# M785dec.net
KiCad netlist of a schematic drawn in EAGLE
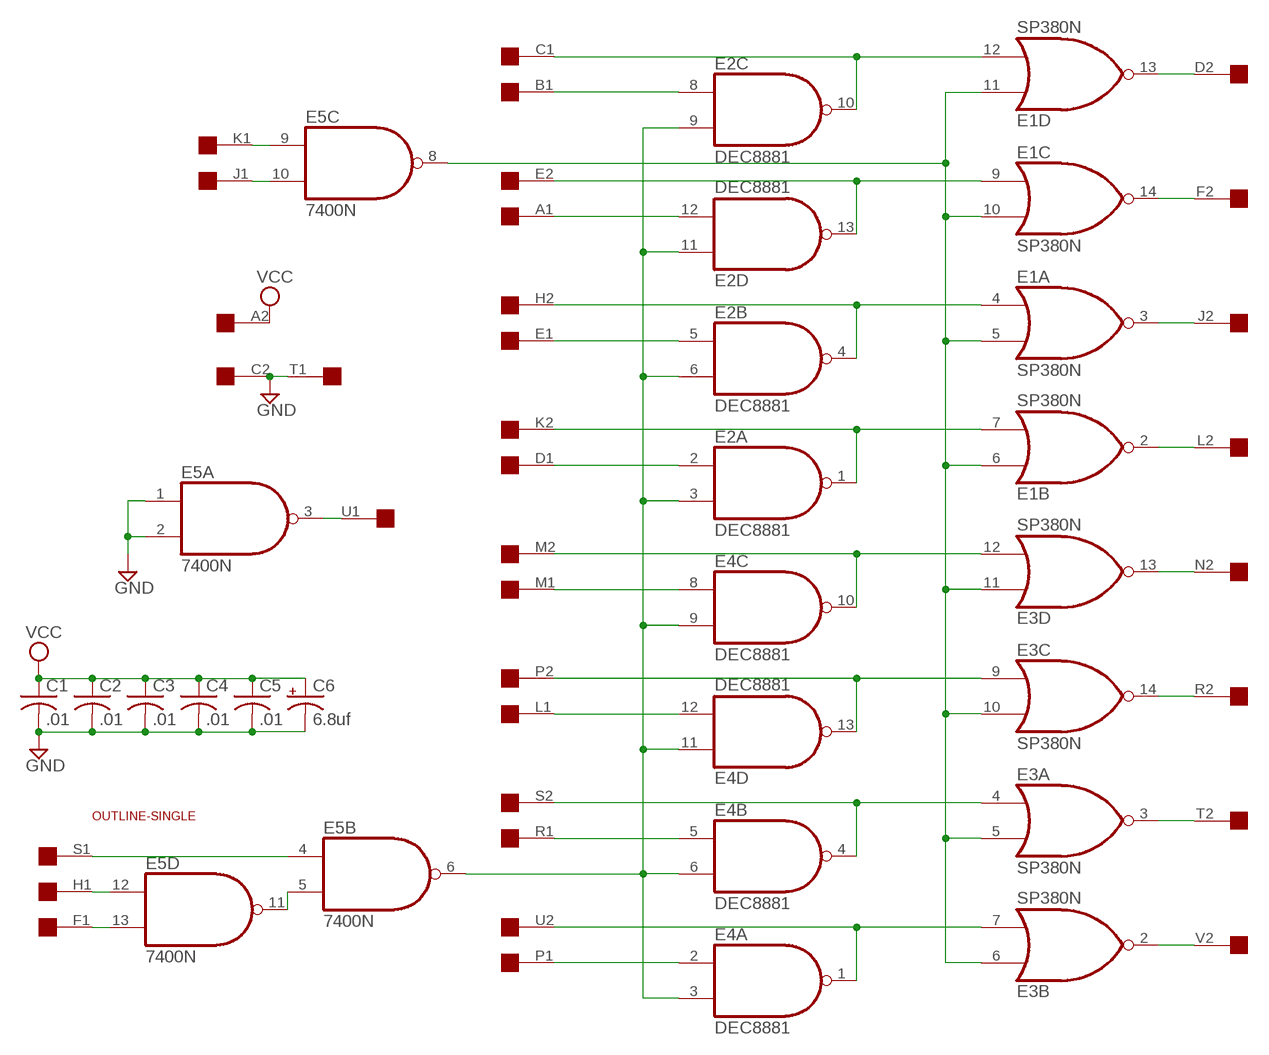
[diagram p0: schematic, sheet 1]

(export (version "E")
  (design (tool "Eeschema 10.0.6"))
  (components
    (comp (ref "C1")
      (value ".01")
      (footprint "eagle-import:C050-025X075")
      (libsource (lib "eagle-import") (part "C-US050-025X075"))
    )
    (comp (ref "C2")
      (value ".01")
      (footprint "eagle-import:C050-025X075")
      (libsource (lib "eagle-import") (part "C-US050-025X075"))
    )
    (comp (ref "C3")
      (value ".01")
      (footprint "eagle-import:C050-025X075")
      (libsource (lib "eagle-import") (part "C-US050-025X075"))
    )
    (comp (ref "C4")
      (value ".01")
      (footprint "eagle-import:C050-025X075")
      (libsource (lib "eagle-import") (part "C-US050-025X075"))
    )
    (comp (ref "C5")
      (value ".01")
      (footprint "eagle-import:C050-025X075")
      (libsource (lib "eagle-import") (part "C-US050-025X075"))
    )
    (comp (ref "C6")
      (value "6.8uf")
      (footprint "eagle-import:E15-5")
      (libsource (lib "eagle-import") (part "CPOL-USE15-5AXIAL"))
    )
    (comp (ref "E1")
      (value "SP380N")
      (footprint "eagle-import:DIL14")
      (libsource (lib "eagle-import") (part "SP380N"))
    )
    (comp (ref "E2")
      (value "DEC8881")
      (footprint "eagle-import:DIL14")
      (libsource (lib "eagle-import") (part "N8881N"))
    )
    (comp (ref "E3")
      (value "SP380N")
      (footprint "eagle-import:DIL14")
      (libsource (lib "eagle-import") (part "SP380N"))
    )
    (comp (ref "E4")
      (value "DEC8881")
      (footprint "eagle-import:DIL14")
      (libsource (lib "eagle-import") (part "N8881N"))
    )
    (comp (ref "E5")
      (value "7400N")
      (footprint "eagle-import:DIL14")
      (libsource (lib "eagle-import") (part "7400N"))
    )
    (comp (ref "U$1")
      (value "SINGLE")
      (footprint "eagle-import:EDGE-CON2")
      (libsource (lib "eagle-import") (part "SINGLE"))
    )
    (comp (ref "U$2")
      (value "OUTLINE-SINGLE")
      (footprint "eagle-import:SINGLE")
      (libsource (lib "eagle-import") (part "OUTLINE-SINGLE"))
    )
  )
  (nets
    (net (code "1") (name "GND") (class "Default")
      (node (ref "C1") (pin "2") (pinfunction "2_2") (pintype "passive"))
      (node (ref "C2") (pin "2") (pinfunction "2_2") (pintype "passive"))
      (node (ref "C3") (pin "2") (pinfunction "2_2") (pintype "passive"))
      (node (ref "C4") (pin "2") (pinfunction "2_2") (pintype "passive"))
      (node (ref "C5") (pin "2") (pinfunction "2_2") (pintype "passive"))
      (node (ref "C6") (pin "-") (pinfunction "-_-") (pintype "passive"))
      (node (ref "E5") (pin "1") (pinfunction "I0_1") (pintype "input"))
      (node (ref "E5") (pin "2") (pinfunction "I1_2") (pintype "input"))
      (node (ref "U$1") (pin "C2") (pinfunction "1_C2") (pintype "bidirectional"))
      (node (ref "U$1") (pin "T1") (pinfunction "1_T1") (pintype "bidirectional"))
    )
    (net (code "2") (name "Net-(E1A-I0)") (class "Default")
      (node (ref "E1") (pin "4") (pinfunction "I0_4") (pintype "input"))
      (node (ref "E2") (pin "4") (pinfunction "O_4") (pintype "open_collector"))
      (node (ref "U$1") (pin "H2") (pinfunction "1_H2") (pintype "bidirectional"))
    )
    (net (code "3") (name "Net-(E1A-I1)") (class "Default")
      (node (ref "E1") (pin "10") (pinfunction "I1_10") (pintype "input"))
      (node (ref "E1") (pin "11") (pinfunction "I0_11") (pintype "input"))
      (node (ref "E1") (pin "5") (pinfunction "I1_5") (pintype "input"))
      (node (ref "E1") (pin "6") (pinfunction "I0_6") (pintype "input"))
      (node (ref "E3") (pin "10") (pinfunction "I1_10") (pintype "input"))
      (node (ref "E3") (pin "11") (pinfunction "I0_11") (pintype "input"))
      (node (ref "E3") (pin "5") (pinfunction "I1_5") (pintype "input"))
      (node (ref "E3") (pin "6") (pinfunction "I0_6") (pintype "input"))
      (node (ref "E5") (pin "8") (pinfunction "O_8") (pintype "output"))
    )
    (net (code "4") (name "Net-(E1A-O)") (class "Default")
      (node (ref "E1") (pin "3") (pinfunction "O_3") (pintype "output"))
      (node (ref "U$1") (pin "J2") (pinfunction "1_J2") (pintype "bidirectional"))
    )
    (net (code "5") (name "Net-(E1B-I1)") (class "Default")
      (node (ref "E1") (pin "7") (pinfunction "I1_7") (pintype "input"))
      (node (ref "E2") (pin "1") (pinfunction "O_1") (pintype "open_collector"))
      (node (ref "U$1") (pin "K2") (pinfunction "1_K2") (pintype "bidirectional"))
    )
    (net (code "6") (name "Net-(E1B-O)") (class "Default")
      (node (ref "E1") (pin "2") (pinfunction "O_2") (pintype "output"))
      (node (ref "U$1") (pin "L2") (pinfunction "1_L2") (pintype "bidirectional"))
    )
    (net (code "7") (name "Net-(E1C-I0)") (class "Default")
      (node (ref "E1") (pin "9") (pinfunction "I0_9") (pintype "input"))
      (node (ref "E2") (pin "13") (pinfunction "O_13") (pintype "open_collector"))
      (node (ref "U$1") (pin "E2") (pinfunction "1_E2") (pintype "bidirectional"))
    )
    (net (code "8") (name "Net-(E1C-O)") (class "Default")
      (node (ref "E1") (pin "14") (pinfunction "O_14") (pintype "output"))
      (node (ref "U$1") (pin "F2") (pinfunction "1_F2") (pintype "bidirectional"))
    )
    (net (code "9") (name "Net-(E1D-I1)") (class "Default")
      (node (ref "E1") (pin "12") (pinfunction "I1_12") (pintype "input"))
      (node (ref "E2") (pin "10") (pinfunction "O_10") (pintype "open_collector"))
      (node (ref "U$1") (pin "C1") (pinfunction "1_C1") (pintype "bidirectional"))
    )
    (net (code "10") (name "Net-(E1D-O)") (class "Default")
      (node (ref "E1") (pin "13") (pinfunction "O_13") (pintype "output"))
      (node (ref "U$1") (pin "D2") (pinfunction "1_D2") (pintype "bidirectional"))
    )
    (net (code "11") (name "Net-(E2A-I0)") (class "Default")
      (node (ref "E2") (pin "2") (pinfunction "I0_2") (pintype "input"))
      (node (ref "U$1") (pin "D1") (pinfunction "1_D1") (pintype "bidirectional"))
    )
    (net (code "12") (name "Net-(E2A-I1)") (class "Default")
      (node (ref "E2") (pin "11") (pinfunction "I0_11") (pintype "input"))
      (node (ref "E2") (pin "3") (pinfunction "I1_3") (pintype "input"))
      (node (ref "E2") (pin "6") (pinfunction "I1_6") (pintype "input"))
      (node (ref "E2") (pin "9") (pinfunction "I1_9") (pintype "input"))
      (node (ref "E4") (pin "11") (pinfunction "I0_11") (pintype "input"))
      (node (ref "E4") (pin "3") (pinfunction "I1_3") (pintype "input"))
      (node (ref "E4") (pin "6") (pinfunction "I1_6") (pintype "input"))
      (node (ref "E4") (pin "9") (pinfunction "I1_9") (pintype "input"))
      (node (ref "E5") (pin "6") (pinfunction "O_6") (pintype "output"))
    )
    (net (code "13") (name "Net-(E2B-I0)") (class "Default")
      (node (ref "E2") (pin "5") (pinfunction "I0_5") (pintype "input"))
      (node (ref "U$1") (pin "E1") (pinfunction "1_E1") (pintype "bidirectional"))
    )
    (net (code "14") (name "Net-(E2C-I0)") (class "Default")
      (node (ref "E2") (pin "8") (pinfunction "I0_8") (pintype "input"))
      (node (ref "U$1") (pin "B1") (pinfunction "1_B1") (pintype "bidirectional"))
    )
    (net (code "15") (name "Net-(E2D-I1)") (class "Default")
      (node (ref "E2") (pin "12") (pinfunction "I1_12") (pintype "input"))
      (node (ref "U$1") (pin "A1") (pinfunction "1_A1") (pintype "bidirectional"))
    )
    (net (code "16") (name "Net-(E3A-I0)") (class "Default")
      (node (ref "E3") (pin "4") (pinfunction "I0_4") (pintype "input"))
      (node (ref "E4") (pin "4") (pinfunction "O_4") (pintype "open_collector"))
      (node (ref "U$1") (pin "S2") (pinfunction "1_S2") (pintype "bidirectional"))
    )
    (net (code "17") (name "Net-(E3A-O)") (class "Default")
      (node (ref "E3") (pin "3") (pinfunction "O_3") (pintype "output"))
      (node (ref "U$1") (pin "T2") (pinfunction "1_T2") (pintype "bidirectional"))
    )
    (net (code "18") (name "Net-(E3B-I1)") (class "Default")
      (node (ref "E3") (pin "7") (pinfunction "I1_7") (pintype "input"))
      (node (ref "E4") (pin "1") (pinfunction "O_1") (pintype "open_collector"))
      (node (ref "U$1") (pin "U2") (pinfunction "1_U2") (pintype "bidirectional"))
    )
    (net (code "19") (name "Net-(E3B-O)") (class "Default")
      (node (ref "E3") (pin "2") (pinfunction "O_2") (pintype "output"))
      (node (ref "U$1") (pin "V2") (pinfunction "1_V2") (pintype "bidirectional"))
    )
    (net (code "20") (name "Net-(E3C-I0)") (class "Default")
      (node (ref "E3") (pin "9") (pinfunction "I0_9") (pintype "input"))
      (node (ref "E4") (pin "13") (pinfunction "O_13") (pintype "open_collector"))
      (node (ref "U$1") (pin "P2") (pinfunction "1_P2") (pintype "bidirectional"))
    )
    (net (code "21") (name "Net-(E3C-O)") (class "Default")
      (node (ref "E3") (pin "14") (pinfunction "O_14") (pintype "output"))
      (node (ref "U$1") (pin "R2") (pinfunction "1_R2") (pintype "bidirectional"))
    )
    (net (code "22") (name "Net-(E3D-I1)") (class "Default")
      (node (ref "E3") (pin "12") (pinfunction "I1_12") (pintype "input"))
      (node (ref "E4") (pin "10") (pinfunction "O_10") (pintype "open_collector"))
      (node (ref "U$1") (pin "M2") (pinfunction "1_M2") (pintype "bidirectional"))
    )
    (net (code "23") (name "Net-(E3D-O)") (class "Default")
      (node (ref "E3") (pin "13") (pinfunction "O_13") (pintype "output"))
      (node (ref "U$1") (pin "N2") (pinfunction "1_N2") (pintype "bidirectional"))
    )
    (net (code "24") (name "Net-(E4A-I0)") (class "Default")
      (node (ref "E4") (pin "2") (pinfunction "I0_2") (pintype "input"))
      (node (ref "U$1") (pin "P1") (pinfunction "1_P1") (pintype "bidirectional"))
    )
    (net (code "25") (name "Net-(E4B-I0)") (class "Default")
      (node (ref "E4") (pin "5") (pinfunction "I0_5") (pintype "input"))
      (node (ref "U$1") (pin "R1") (pinfunction "1_R1") (pintype "bidirectional"))
    )
    (net (code "26") (name "Net-(E4C-I0)") (class "Default")
      (node (ref "E4") (pin "8") (pinfunction "I0_8") (pintype "input"))
      (node (ref "U$1") (pin "M1") (pinfunction "1_M1") (pintype "bidirectional"))
    )
    (net (code "27") (name "Net-(E4D-I1)") (class "Default")
      (node (ref "E4") (pin "12") (pinfunction "I1_12") (pintype "input"))
      (node (ref "U$1") (pin "L1") (pinfunction "1_L1") (pintype "bidirectional"))
    )
    (net (code "28") (name "Net-(E5A-O)") (class "Default")
      (node (ref "E5") (pin "3") (pinfunction "O_3") (pintype "output"))
      (node (ref "U$1") (pin "U1") (pinfunction "1_U1") (pintype "bidirectional"))
    )
    (net (code "29") (name "Net-(E5B-I0)") (class "Default")
      (node (ref "E5") (pin "4") (pinfunction "I0_4") (pintype "input"))
      (node (ref "U$1") (pin "S1") (pinfunction "1_S1") (pintype "bidirectional"))
    )
    (net (code "30") (name "Net-(E5B-I1)") (class "Default")
      (node (ref "E5") (pin "11") (pinfunction "O_11") (pintype "output"))
      (node (ref "E5") (pin "5") (pinfunction "I1_5") (pintype "input"))
    )
    (net (code "31") (name "Net-(E5C-I0)") (class "Default")
      (node (ref "E5") (pin "9") (pinfunction "I0_9") (pintype "input"))
      (node (ref "U$1") (pin "K1") (pinfunction "1_K1") (pintype "bidirectional"))
    )
    (net (code "32") (name "Net-(E5C-I1)") (class "Default")
      (node (ref "E5") (pin "10") (pinfunction "I1_10") (pintype "input"))
      (node (ref "U$1") (pin "J1") (pinfunction "1_J1") (pintype "bidirectional"))
    )
    (net (code "33") (name "Net-(E5D-I0)") (class "Default")
      (node (ref "E5") (pin "12") (pinfunction "I0_12") (pintype "input"))
      (node (ref "U$1") (pin "H1") (pinfunction "1_H1") (pintype "bidirectional"))
    )
    (net (code "34") (name "Net-(E5D-I1)") (class "Default")
      (node (ref "E5") (pin "13") (pinfunction "I1_13") (pintype "input"))
      (node (ref "U$1") (pin "F1") (pinfunction "1_F1") (pintype "bidirectional"))
    )
    (net (code "35") (name "VCC") (class "Default")
      (node (ref "C1") (pin "1") (pinfunction "1_1") (pintype "passive"))
      (node (ref "C2") (pin "1") (pinfunction "1_1") (pintype "passive"))
      (node (ref "C3") (pin "1") (pinfunction "1_1") (pintype "passive"))
      (node (ref "C4") (pin "1") (pinfunction "1_1") (pintype "passive"))
      (node (ref "C5") (pin "1") (pinfunction "1_1") (pintype "passive"))
      (node (ref "C6") (pin "+") (pinfunction "+_+") (pintype "passive"))
      (node (ref "U$1") (pin "A2") (pinfunction "1_A2") (pintype "bidirectional"))
    )
  )
)
